# ESP8266_ClockLed.net
KiCad netlist of a schematic drawn in Altium Designer
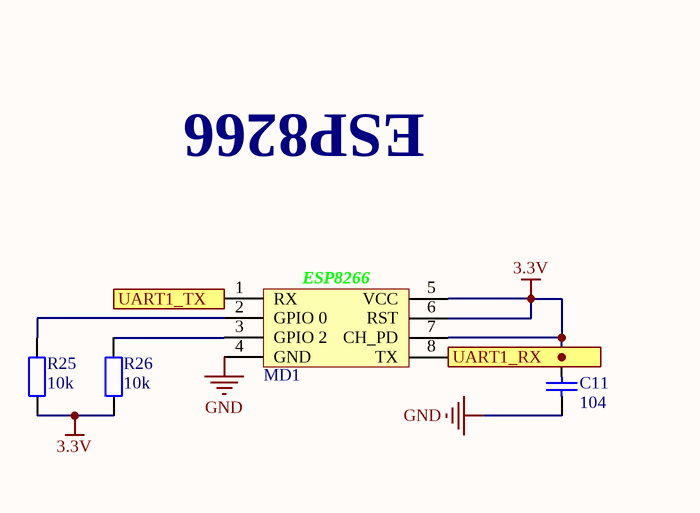
[diagram p0: ESP8266_ClockLed.SchDoc]

(export (version "E")
  (design (tool "Eeschema 10.0.6"))
  (components
    (comp (ref "C11")
      (value "104")
      (footprint "tu 0805")
      (description "Dán")
      (libsource (lib "Altium_Lib_by_KhueNguyenCreator") (part "Tu 0805 104 50V 10%"))
    )
    (comp (ref "MD1")
      (value "ESP8266 Module")
      (footprint "ESP2866 Module")
      (libsource (lib "Altium_Lib_by_KhueNguyenCreator") (part "ESP8266 Module"))
    )
    (comp (ref "R25")
      (value "10k")
      (footprint "tro smd 0805")
      (description "Dán")
      (libsource (lib "Altium_Lib_by_KhueNguyenCreator") (part "Tro 0805 5% 10k"))
    )
    (comp (ref "R26")
      (value "10k")
      (footprint "tro smd 0805")
      (description "Dán")
      (libsource (lib "Altium_Lib_by_KhueNguyenCreator") (part "Tro 0805 5% 10k"))
    )
  )
  (nets
    (net (code "1") (name "/UART1_RX") (class "Default")
      (node (ref "MD1") (pin "8") (pinfunction "TX_8") (pintype "passive"))
    )
    (net (code "2") (name "/UART1_TX") (class "Default")
      (node (ref "MD1") (pin "1") (pinfunction "RX_1") (pintype "passive"))
    )
    (net (code "3") (name "3.3V") (class "Default")
      (node (ref "C11") (pin "2") (pinfunction "2_2") (pintype "passive"))
      (node (ref "MD1") (pin "5") (pinfunction "VCC_5") (pintype "passive"))
      (node (ref "MD1") (pin "6") (pinfunction "RST_6") (pintype "passive"))
      (node (ref "MD1") (pin "7") (pinfunction "CH_PD_7") (pintype "passive"))
      (node (ref "R25") (pin "1") (pinfunction "1_1") (pintype "passive"))
      (node (ref "R26") (pin "1") (pinfunction "1_1") (pintype "passive"))
    )
    (net (code "4") (name "GND") (class "Default")
      (node (ref "C11") (pin "1") (pinfunction "1_1") (pintype "passive"))
      (node (ref "MD1") (pin "4") (pinfunction "GND_4") (pintype "passive"))
    )
    (net (code "5") (name "Net-(MD1-GPIO_0)") (class "Default")
      (node (ref "MD1") (pin "2") (pinfunction "GPIO_0_2") (pintype "passive"))
      (node (ref "R25") (pin "2") (pinfunction "2_2") (pintype "passive"))
    )
    (net (code "6") (name "Net-(MD1-GPIO_2)") (class "Default")
      (node (ref "MD1") (pin "3") (pinfunction "GPIO_2_3") (pintype "passive"))
      (node (ref "R26") (pin "2") (pinfunction "2_2") (pintype "passive"))
    )
  )
)
